# Zapper.net
KiCad netlist of a schematic drawn in Altium Designer
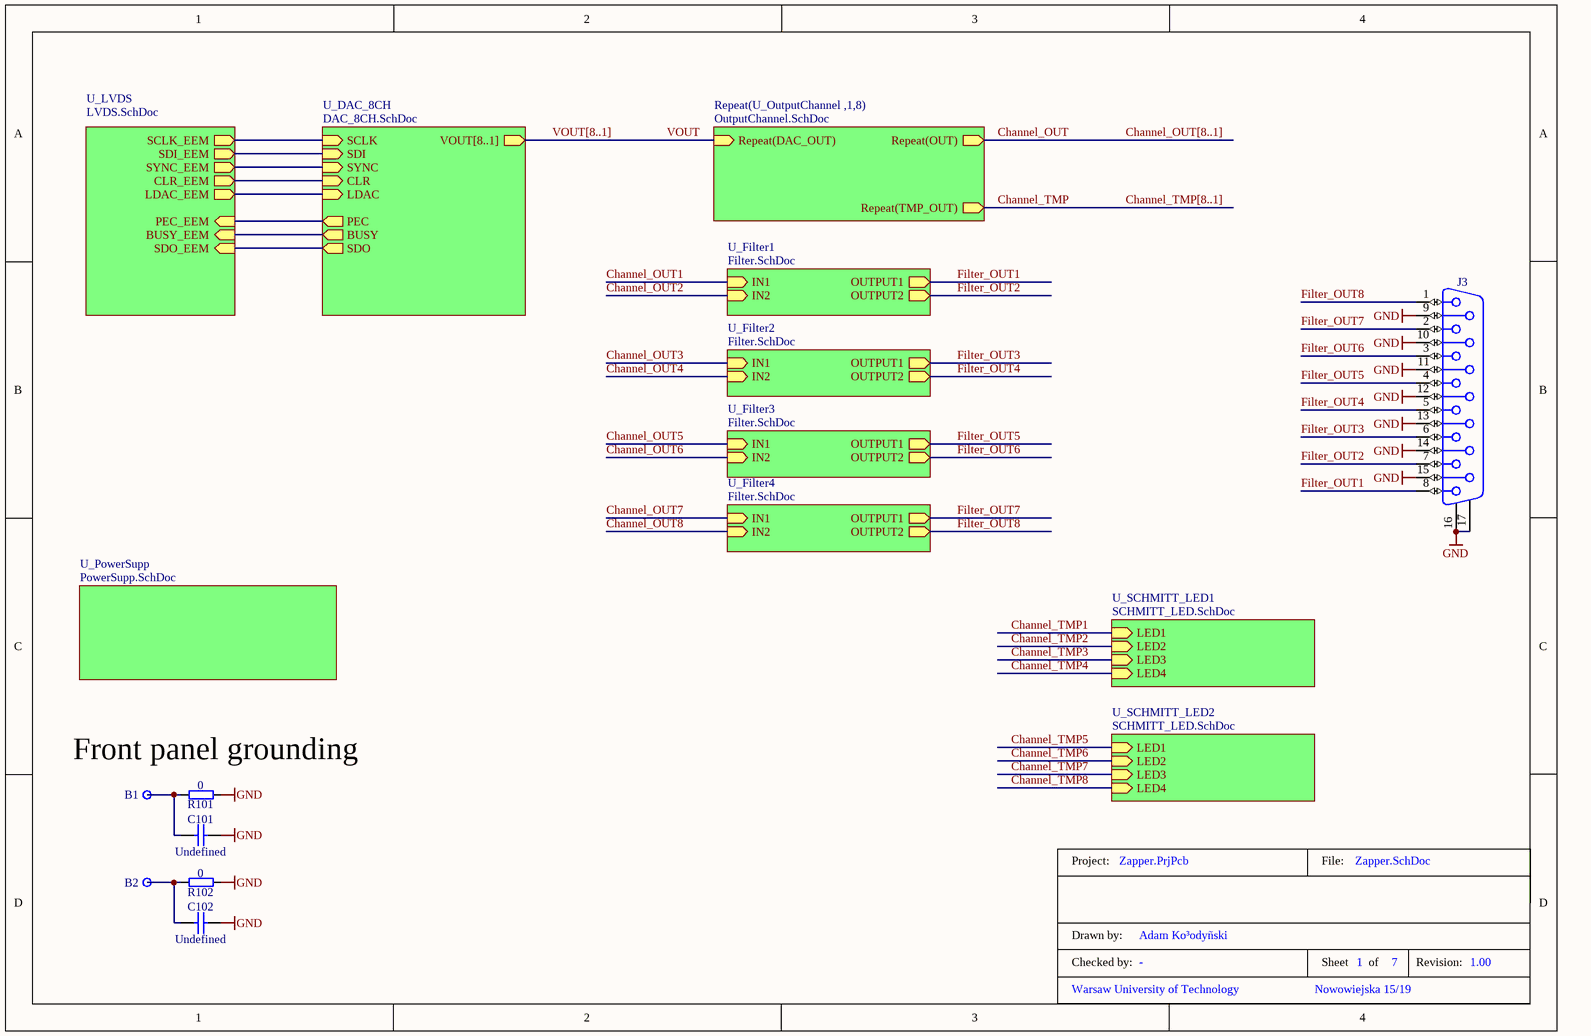
[diagram p0: Zapper.SchDoc]

(export (version "E")
  (design (tool "Eeschema 10.0.6"))
  (components
    (comp (ref "B1")
      (value "Plated Hole")
      (footprint "MTG270_500")
      (description "Single Terminal Socket")
      (fields (field (name "PART NUMBER") "PLATED_HOLE2.7_PAD5.0") (field (name "AUTHOR") "CERN DEM JMW"))
      (libsource (lib "Eletro-mechanical") (part "Single Terminal Socket"))
    )
    (comp (ref "B2")
      (value "Plated Hole")
      (footprint "MTG270_500")
      (description "Single Terminal Socket")
      (fields (field (name "PART NUMBER") "PLATED_HOLE2.7_PAD5.0") (field (name "AUTHOR") "CERN DEM JMW"))
      (libsource (lib "Eletro-mechanical") (part "Single Terminal Socket"))
    )
    (comp (ref "C101")
      (value "Undefined")
      (footprint "CAPC2012X135N")
      (description "Non-polarised capacitor")
      (fields (field (name "PART NUMBER") "CC0805_NO-VALUE") (field (name "AUTHOR") "CERN DEM JLC"))
      (libsource (lib "Capacitors") (part "Capacitor - non polarized"))
    )
    (comp (ref "C102")
      (value "Undefined")
      (footprint "CAPC2012X135N")
      (description "Non-polarised capacitor")
      (fields (field (name "PART NUMBER") "CC0805_NO-VALUE") (field (name "AUTHOR") "CERN DEM JLC"))
      (libsource (lib "Capacitors") (part "Capacitor - non polarized"))
    )
    (comp (ref "J3")
      (value "D-Sub 15F")
      (footprint "HARTING_09 66 252 6612")
      (description "Connector D-sub 15 Female")
      (fields
        (field (name "PART NUMBER") "HARTING_09 66 252 6612")
        (field (name "MANUFACTURER") "HARTING")
        (field (name "AUTHOR") "CERN DEM JLC")
      )
      (libsource (lib "Connectors") (part "Connector D-sub 15 Female"))
    )
    (comp (ref "R101")
      (value "0")
      (footprint "RESC1608X55N")
      (description "Resistor")
      (fields
        (field (name "PART NUMBER") "R0603_0R_JUMPER")
        (field (name "MANUFACTURER") "GENERIC")
        (field (name "AUTHOR") "CERN DEM JLC")
      )
      (libsource (lib "Resistors") (part "Resistor"))
    )
    (comp (ref "R102")
      (value "0")
      (footprint "RESC1608X55N")
      (description "Resistor")
      (fields
        (field (name "PART NUMBER") "R0603_0R_JUMPER")
        (field (name "MANUFACTURER") "GENERIC")
        (field (name "AUTHOR") "CERN DEM JLC")
      )
      (libsource (lib "Resistors") (part "Resistor"))
    )
    (comp (ref "TitleBlock1") (value "TitleBlock") (libsource (lib "InzLib") (part "TitleBlock")))
  )
  (nets
    (net (code "31") (name "/Filter_OUT1") (class "Default")
      (node (ref "J3") (pin "8") (pinfunction "8_8") (pintype "bidirectional"))
    )
    (net (code "32") (name "/Filter_OUT2") (class "Default")
      (node (ref "J3") (pin "7") (pinfunction "7_7") (pintype "bidirectional"))
    )
    (net (code "33") (name "/Filter_OUT3") (class "Default")
      (node (ref "J3") (pin "6") (pinfunction "6_6") (pintype "bidirectional"))
    )
    (net (code "34") (name "/Filter_OUT4") (class "Default")
      (node (ref "J3") (pin "5") (pinfunction "5_5") (pintype "bidirectional"))
    )
    (net (code "35") (name "/Filter_OUT5") (class "Default")
      (node (ref "J3") (pin "4") (pinfunction "4_4") (pintype "bidirectional"))
    )
    (net (code "36") (name "/Filter_OUT6") (class "Default")
      (node (ref "J3") (pin "3") (pinfunction "3_3") (pintype "bidirectional"))
    )
    (net (code "37") (name "/Filter_OUT7") (class "Default")
      (node (ref "J3") (pin "2") (pinfunction "2_2") (pintype "bidirectional"))
    )
    (net (code "38") (name "/Filter_OUT8") (class "Default")
      (node (ref "J3") (pin "1") (pinfunction "1_1") (pintype "bidirectional"))
    )
    (net (code "47") (name "GND") (class "Default")
      (node (ref "C101") (pin "2") (pinfunction "2_2") (pintype "passive"))
      (node (ref "C102") (pin "2") (pinfunction "2_2") (pintype "passive"))
      (node (ref "J3") (pin "10") (pinfunction "10_10") (pintype "bidirectional"))
      (node (ref "J3") (pin "11") (pinfunction "11_11") (pintype "bidirectional"))
      (node (ref "J3") (pin "12") (pinfunction "12_12") (pintype "bidirectional"))
      (node (ref "J3") (pin "13") (pinfunction "13_13") (pintype "bidirectional"))
      (node (ref "J3") (pin "14") (pinfunction "14_14") (pintype "bidirectional"))
      (node (ref "J3") (pin "15") (pinfunction "15_15") (pintype "bidirectional"))
      (node (ref "J3") (pin "16") (pinfunction "16_16") (pintype "passive"))
      (node (ref "J3") (pin "17") (pinfunction "17_17") (pintype "passive"))
      (node (ref "J3") (pin "9") (pinfunction "9_9") (pintype "bidirectional"))
      (node (ref "R101") (pin "1") (pinfunction "1_1") (pintype "passive"))
      (node (ref "R102") (pin "1") (pinfunction "1_1") (pintype "passive"))
    )
    (net (code "48") (name "Net-(B1-Pad1)") (class "Default")
      (node (ref "B1") (pin "1") (pinfunction "1_1") (pintype "bidirectional"))
      (node (ref "C101") (pin "1") (pinfunction "1_1") (pintype "passive"))
      (node (ref "R101") (pin "2") (pinfunction "2_2") (pintype "passive"))
    )
    (net (code "49") (name "Net-(B2-Pad1)") (class "Default")
      (node (ref "B2") (pin "1") (pinfunction "1_1") (pintype "bidirectional"))
      (node (ref "C102") (pin "1") (pinfunction "1_1") (pintype "passive"))
      (node (ref "R102") (pin "2") (pinfunction "2_2") (pintype "passive"))
    )
  )
)
